# pca10040_sheet3_pin_map.net
KiCad netlist of a schematic drawn in Altium Designer
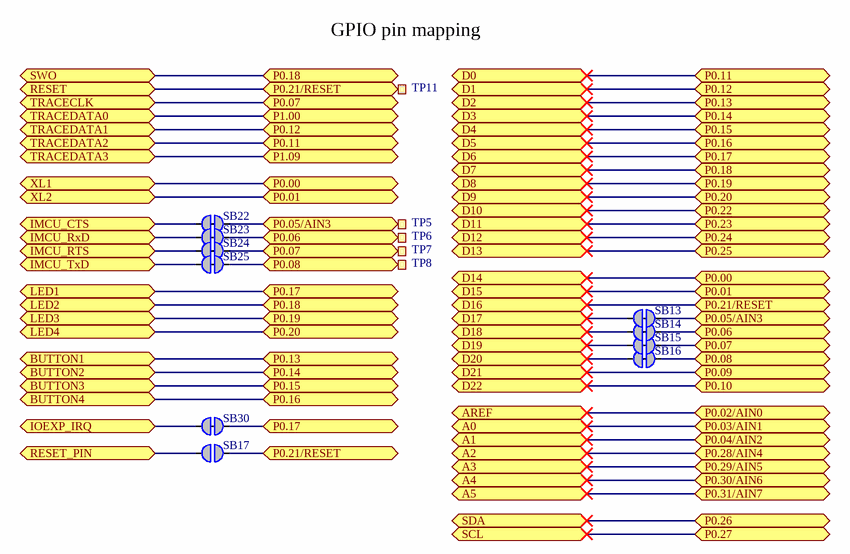
[diagram p0: pca10040_sheet3_pin_map.SchDoc]

(export (version "E")
  (design (tool "Eeschema 10.0.6"))
  (components
    (comp (ref "SB13")
      (value "Solderbridge")
      (footprint "Solderbridge_Shorted")
      (description "Shorted Solderbridge")
      (fields
        (field (name "PART NUMBER") "Solderbridge Shorted")
        (field (name "PUBLISHER") "Nordic Semiconductor")
      )
      (libsource (lib "Nordic Passive DB") (part "SOLDERBRIDGE_SHORTED"))
    )
    (comp (ref "SB14")
      (value "Solderbridge")
      (footprint "Solderbridge_Shorted")
      (description "Shorted Solderbridge")
      (fields
        (field (name "PART NUMBER") "Solderbridge Shorted")
        (field (name "PUBLISHER") "Nordic Semiconductor")
      )
      (libsource (lib "Nordic Passive DB") (part "SOLDERBRIDGE_SHORTED"))
    )
    (comp (ref "SB15")
      (value "Solderbridge")
      (footprint "Solderbridge_Shorted")
      (description "Shorted Solderbridge")
      (fields
        (field (name "PART NUMBER") "Solderbridge Shorted")
        (field (name "PUBLISHER") "Nordic Semiconductor")
      )
      (libsource (lib "Nordic Passive DB") (part "SOLDERBRIDGE_SHORTED"))
    )
    (comp (ref "SB16")
      (value "Solderbridge")
      (footprint "Solderbridge_Shorted")
      (description "Shorted Solderbridge")
      (fields
        (field (name "PART NUMBER") "Solderbridge Shorted")
        (field (name "PUBLISHER") "Nordic Semiconductor")
      )
      (libsource (lib "Nordic Passive DB") (part "SOLDERBRIDGE_SHORTED"))
    )
    (comp (ref "SB17")
      (value "Solderbridge")
      (footprint "Solderbridge")
      (fields (field (name "PUBLISHER") "Nordic Semiconductor"))
      (libsource (lib "Nordic Passive DB") (part "SOLDERBRIDGE"))
    )
    (comp (ref "SB22")
      (value "Solderbridge")
      (footprint "Solderbridge_Shorted")
      (description "Shorted Solderbridge")
      (fields
        (field (name "PART NUMBER") "Solderbridge Shorted")
        (field (name "PUBLISHER") "Nordic Semiconductor")
      )
      (libsource (lib "Nordic Passive DB") (part "SOLDERBRIDGE_SHORTED"))
    )
    (comp (ref "SB23")
      (value "Solderbridge")
      (footprint "Solderbridge_Shorted")
      (description "Shorted Solderbridge")
      (fields
        (field (name "PART NUMBER") "Solderbridge Shorted")
        (field (name "PUBLISHER") "Nordic Semiconductor")
      )
      (libsource (lib "Nordic Passive DB") (part "SOLDERBRIDGE_SHORTED"))
    )
    (comp (ref "SB24")
      (value "Solderbridge")
      (footprint "Solderbridge_Shorted")
      (description "Shorted Solderbridge")
      (fields
        (field (name "PART NUMBER") "Solderbridge Shorted")
        (field (name "PUBLISHER") "Nordic Semiconductor")
      )
      (libsource (lib "Nordic Passive DB") (part "SOLDERBRIDGE_SHORTED"))
    )
    (comp (ref "SB25")
      (value "Solderbridge")
      (footprint "Solderbridge_Shorted")
      (description "Shorted Solderbridge")
      (fields
        (field (name "PART NUMBER") "Solderbridge Shorted")
        (field (name "PUBLISHER") "Nordic Semiconductor")
      )
      (libsource (lib "Nordic Passive DB") (part "SOLDERBRIDGE_SHORTED"))
    )
    (comp (ref "SB30")
      (value "Solderbridge")
      (footprint "Solderbridge_Shorted")
      (description "Shorted Solderbridge")
      (fields
        (field (name "PART NUMBER") "Solderbridge Shorted")
        (field (name "PUBLISHER") "Nordic Semiconductor")
      )
      (libsource (lib "Nordic Passive DB") (part "SOLDERBRIDGE_SHORTED"))
    )
    (comp (ref "TP5")
      (value "Ø1.0mm,SMD")
      (footprint "TP_SMD_Ø1.0mm")
      (description "1.0mm circular SMD testpad")
      (fields
        (field (name "PART NUMBER") "TP_SMD_Ø1.0MM")
        (field (name "MANUFACTURER") "Nordic Semiconductor")
        (field (name "PUBLISHER") "Nordic Semiconductor")
      )
      (libsource (lib "Nordic Passive DB") (part "TESTPAD"))
    )
    (comp (ref "TP6")
      (value "Ø1.0mm,SMD")
      (footprint "TP_SMD_Ø1.0mm")
      (description "1.0mm circular SMD testpad")
      (fields
        (field (name "PART NUMBER") "TP_SMD_Ø1.0MM")
        (field (name "MANUFACTURER") "Nordic Semiconductor")
        (field (name "PUBLISHER") "Nordic Semiconductor")
      )
      (libsource (lib "Nordic Passive DB") (part "TESTPAD"))
    )
    (comp (ref "TP7")
      (value "Ø1.0mm,SMD")
      (footprint "TP_SMD_Ø1.0mm")
      (description "1.0mm circular SMD testpad")
      (fields
        (field (name "PART NUMBER") "TP_SMD_Ø1.0MM")
        (field (name "MANUFACTURER") "Nordic Semiconductor")
        (field (name "PUBLISHER") "Nordic Semiconductor")
      )
      (libsource (lib "Nordic Passive DB") (part "TESTPAD"))
    )
    (comp (ref "TP8")
      (value "Ø1.0mm,SMD")
      (footprint "TP_SMD_Ø1.0mm")
      (description "1.0mm circular SMD testpad")
      (fields
        (field (name "PART NUMBER") "TP_SMD_Ø1.0MM")
        (field (name "MANUFACTURER") "Nordic Semiconductor")
        (field (name "PUBLISHER") "Nordic Semiconductor")
      )
      (libsource (lib "Nordic Passive DB") (part "TESTPAD"))
    )
    (comp (ref "TP11")
      (value "Ø1.0mm,SMD")
      (footprint "TP_SMD_Ø1.0mm")
      (description "1.0mm circular SMD testpad")
      (fields
        (field (name "PART NUMBER") "TP_SMD_Ø1.0MM")
        (field (name "MANUFACTURER") "Nordic Semiconductor")
        (field (name "PUBLISHER") "Nordic Semiconductor")
      )
      (libsource (lib "Nordic Passive DB") (part "TESTPAD"))
    )
  )
  (nets
    (net (code "14") (name "/D6") (class "Default")
      (node (ref "SB30") (pin "1") (pinfunction "0_1") (pintype "passive"))
    )
    (net (code "24") (name "/D16") (class "Default")
      (node (ref "SB17") (pin "2") (pinfunction "1_2") (pintype "passive"))
      (node (ref "TP11") (pin "1") (pinfunction "1_1") (pintype "passive"))
    )
    (net (code "25") (name "/D17") (class "Default")
      (node (ref "SB13") (pin "1") (pinfunction "0_1") (pintype "passive+no_connect"))
    )
    (net (code "26") (name "/D18") (class "Default")
      (node (ref "SB14") (pin "1") (pinfunction "0_1") (pintype "passive+no_connect"))
    )
    (net (code "27") (name "/D19") (class "Default")
      (node (ref "SB15") (pin "1") (pinfunction "0_1") (pintype "passive+no_connect"))
    )
    (net (code "28") (name "/D20") (class "Default")
      (node (ref "SB16") (pin "1") (pinfunction "0_1") (pintype "passive+no_connect"))
    )
    (net (code "31") (name "/IMCU_CTS") (class "Default")
      (node (ref "SB22") (pin "2") (pinfunction "1_2") (pintype "passive"))
    )
    (net (code "32") (name "/IMCU_RTS") (class "Default")
      (node (ref "SB24") (pin "2") (pinfunction "1_2") (pintype "passive"))
    )
    (net (code "33") (name "/IMCU_RxD") (class "Default")
      (node (ref "SB23") (pin "2") (pinfunction "1_2") (pintype "passive"))
    )
    (net (code "34") (name "/IMCU_TxD") (class "Default")
      (node (ref "SB25") (pin "2") (pinfunction "1_2") (pintype "passive"))
    )
    (net (code "35") (name "/IOEXP_IRQ") (class "Default")
      (node (ref "SB30") (pin "2") (pinfunction "1_2") (pintype "passive"))
    )
    (net (code "36") (name "/P0.05{slash}AIN3") (class "Default")
      (node (ref "SB13") (pin "2") (pinfunction "1_2") (pintype "passive"))
      (node (ref "SB22") (pin "1") (pinfunction "0_1") (pintype "passive"))
      (node (ref "TP5") (pin "1") (pinfunction "1_1") (pintype "passive"))
    )
    (net (code "37") (name "/P0.06") (class "Default")
      (node (ref "SB14") (pin "2") (pinfunction "1_2") (pintype "passive"))
      (node (ref "SB23") (pin "1") (pinfunction "0_1") (pintype "passive"))
      (node (ref "TP6") (pin "1") (pinfunction "1_1") (pintype "passive"))
    )
    (net (code "38") (name "/P0.07") (class "Default")
      (node (ref "SB15") (pin "2") (pinfunction "1_2") (pintype "passive"))
      (node (ref "SB24") (pin "1") (pinfunction "0_1") (pintype "passive"))
      (node (ref "TP7") (pin "1") (pinfunction "1_1") (pintype "passive"))
    )
    (net (code "39") (name "/P0.08") (class "Default")
      (node (ref "SB16") (pin "2") (pinfunction "1_2") (pintype "passive"))
      (node (ref "SB25") (pin "1") (pinfunction "0_1") (pintype "passive"))
      (node (ref "TP8") (pin "1") (pinfunction "1_1") (pintype "passive"))
    )
    (net (code "44") (name "/RESET_PIN") (class "Default")
      (node (ref "SB17") (pin "1") (pinfunction "0_1") (pintype "passive"))
    )
  )
)
